# MSP-EXP430FR5994_EagleCAD.net
KiCad netlist of a schematic drawn in EAGLE
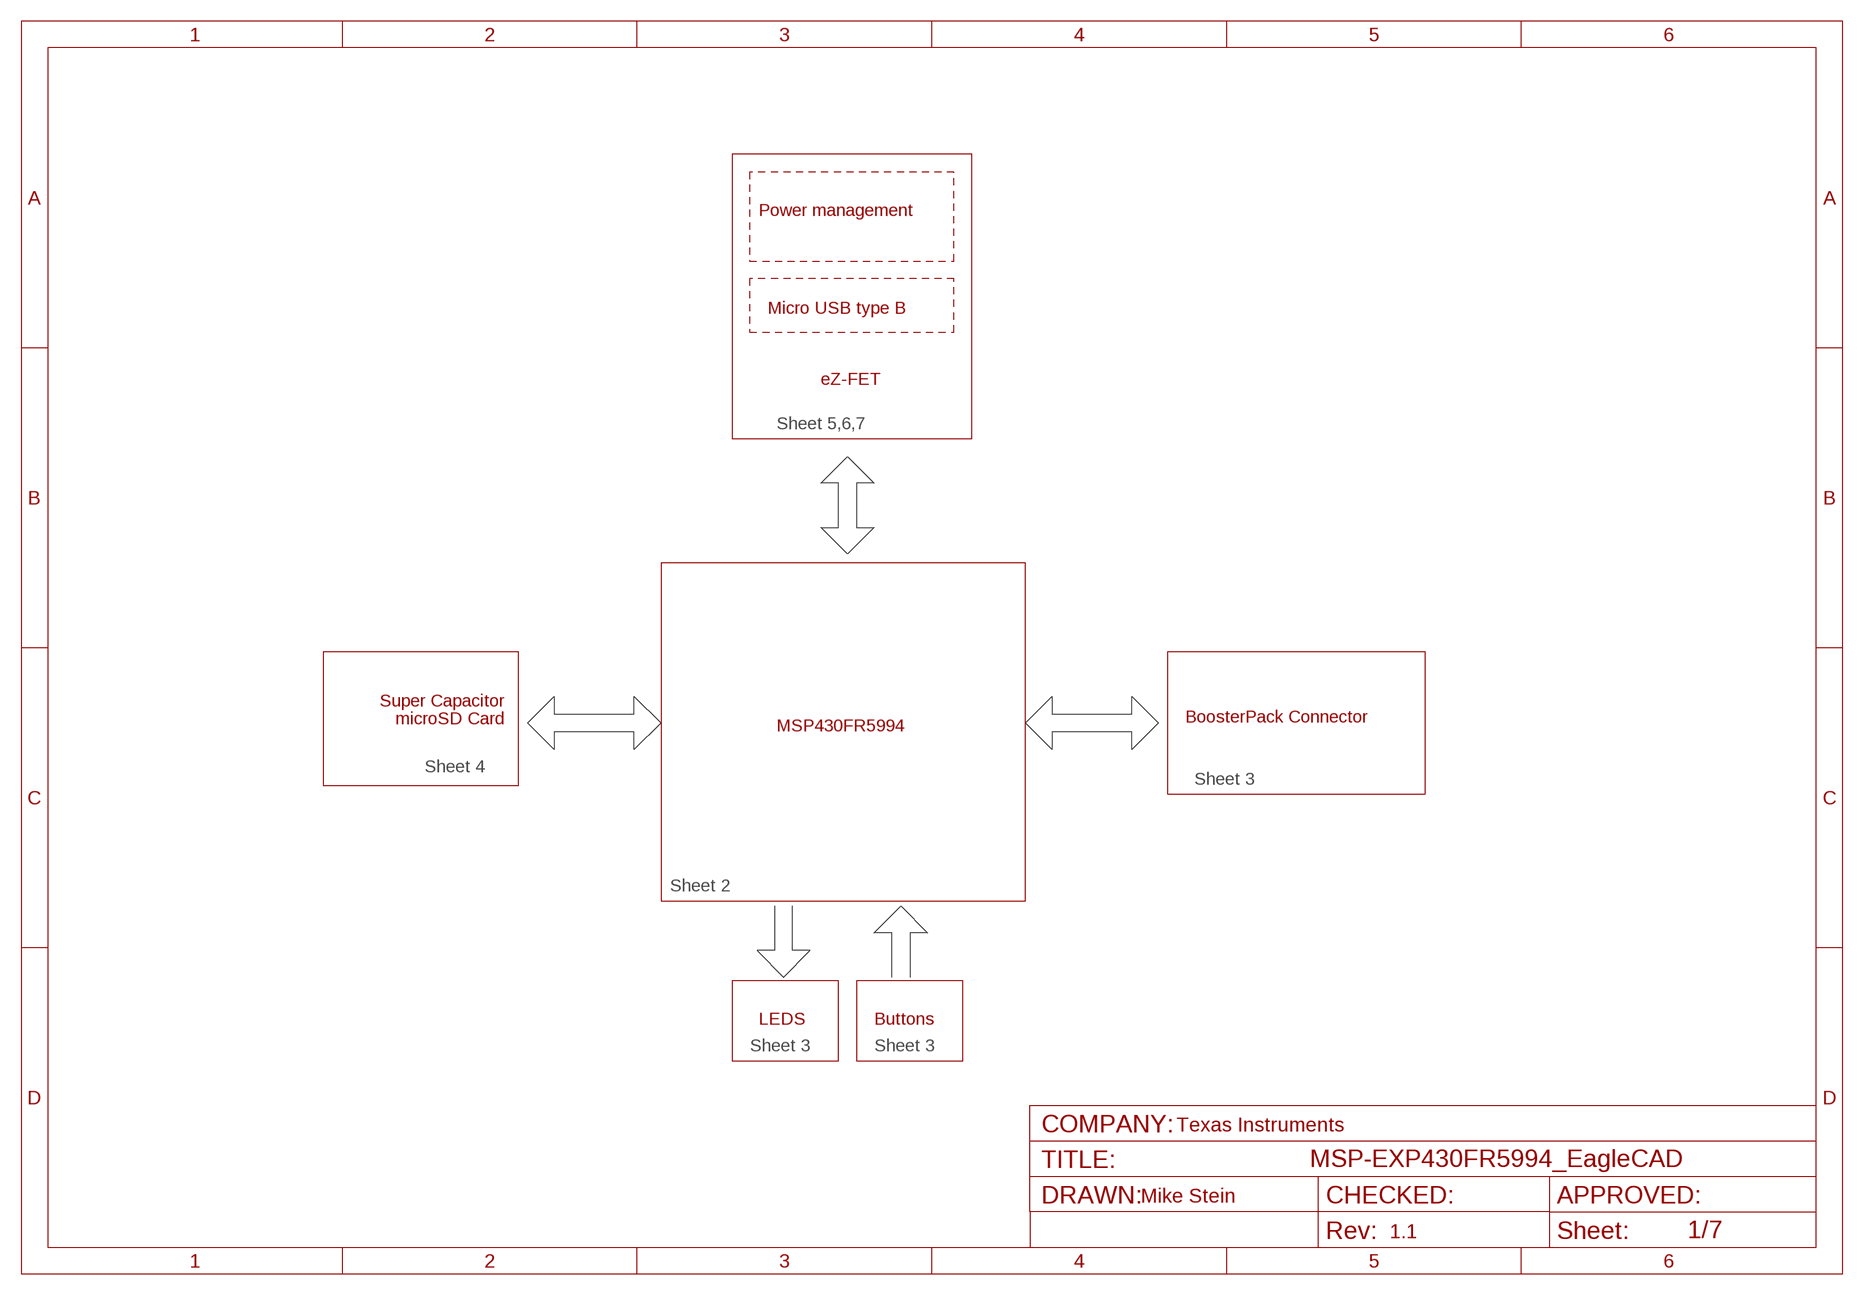
[diagram p0: schematic, sheet 1]
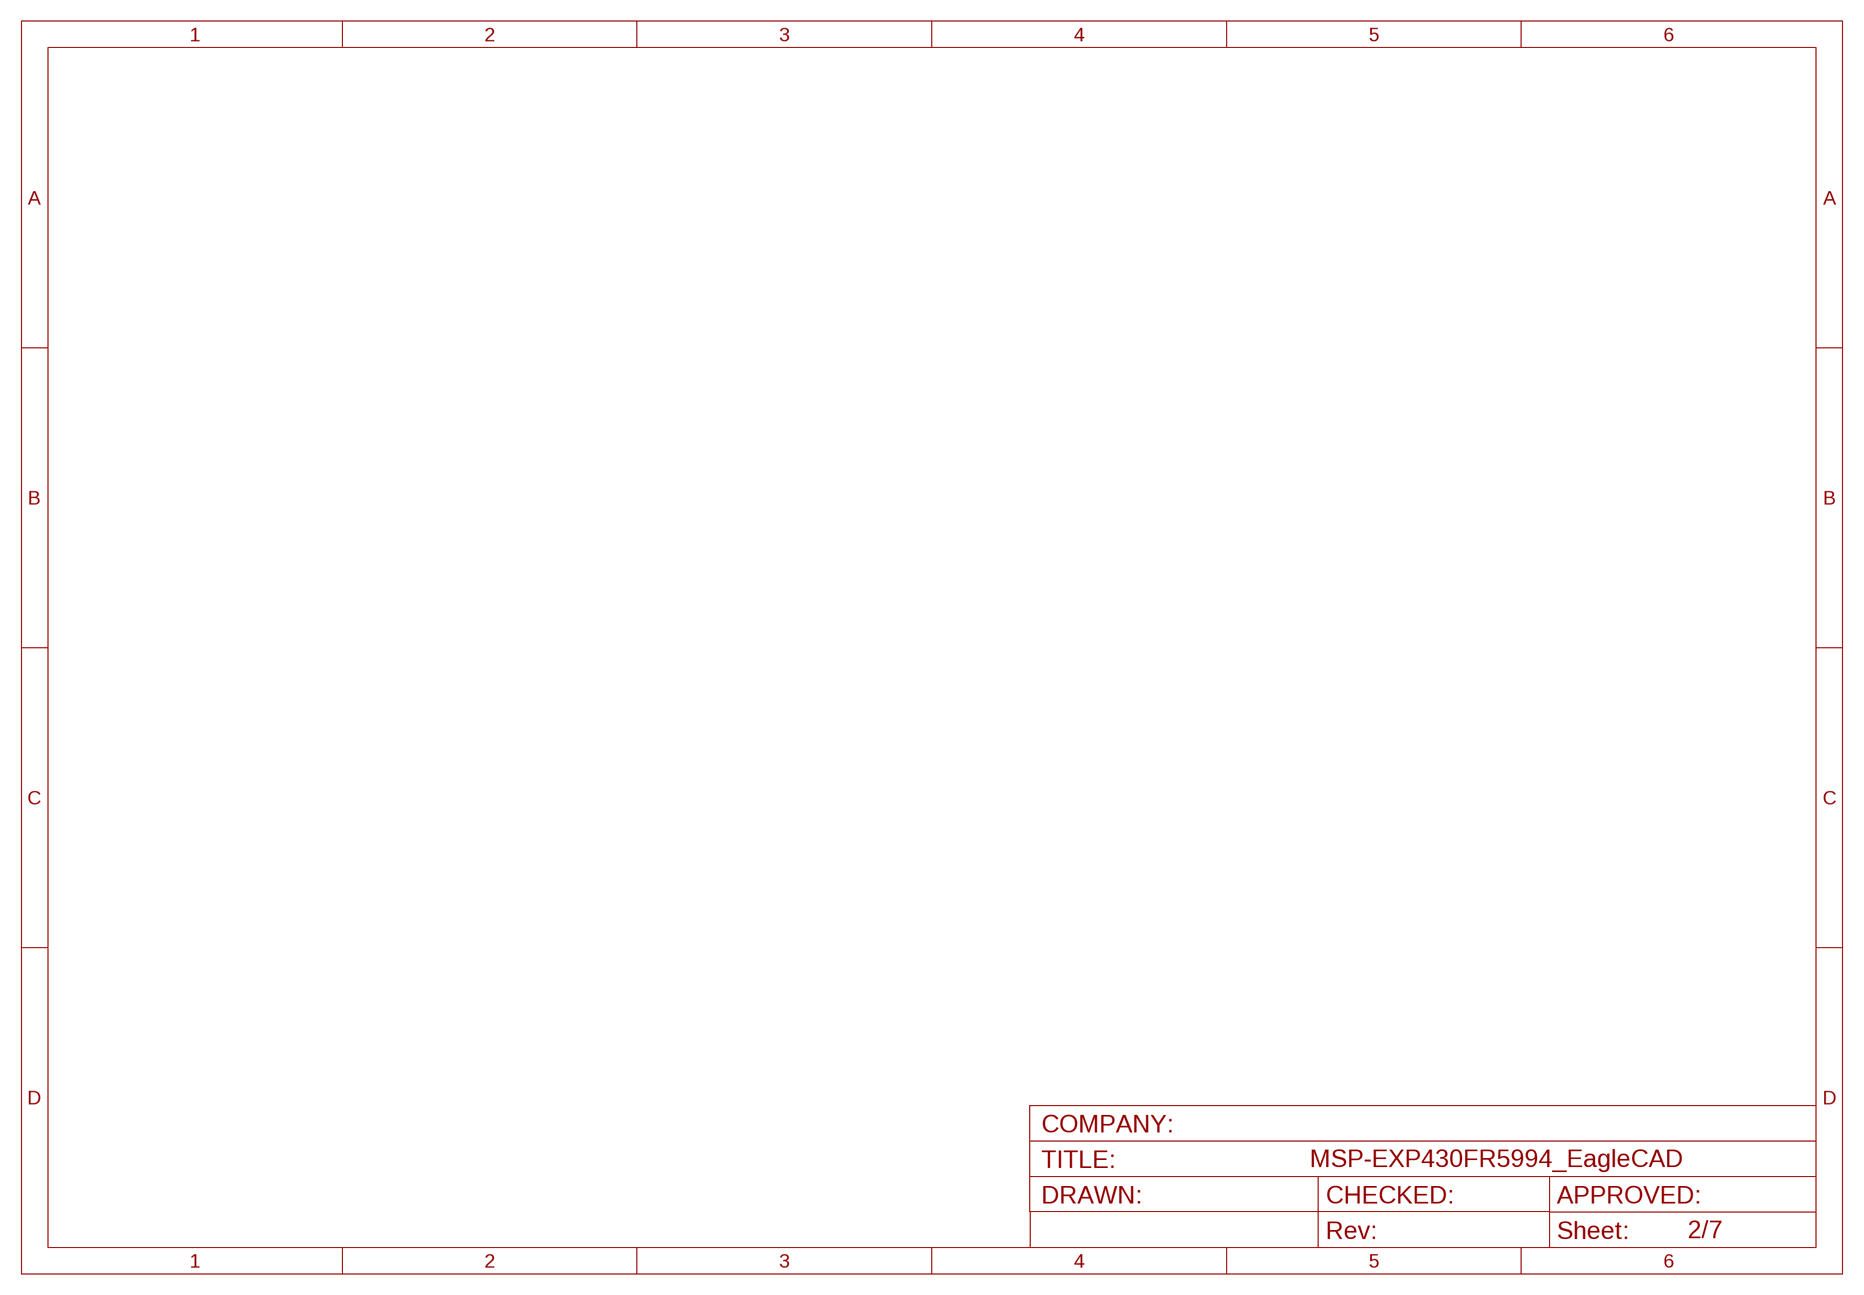
[diagram p1: schematic, sheet 2]
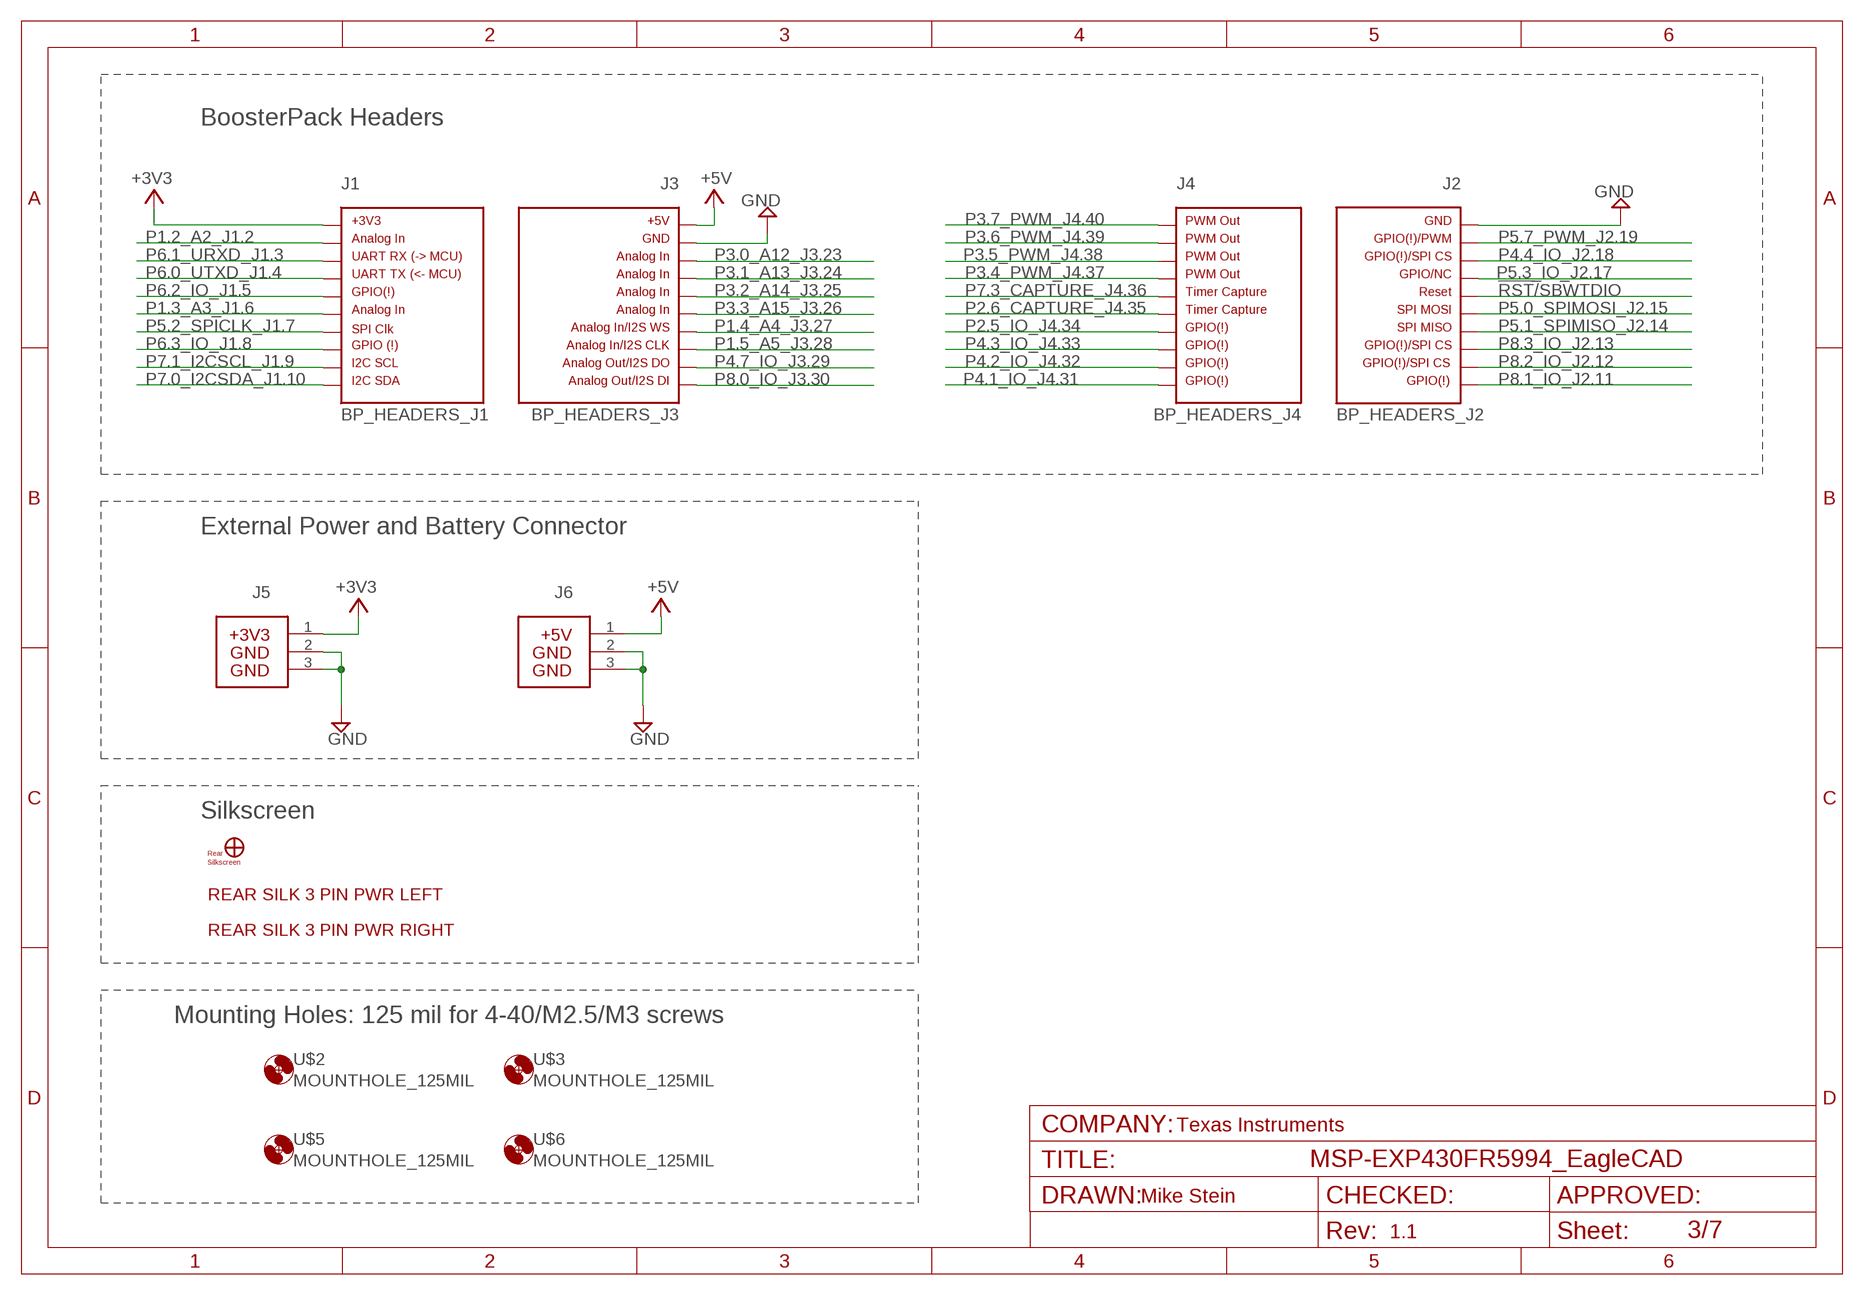
[diagram p2: schematic, sheet 3]
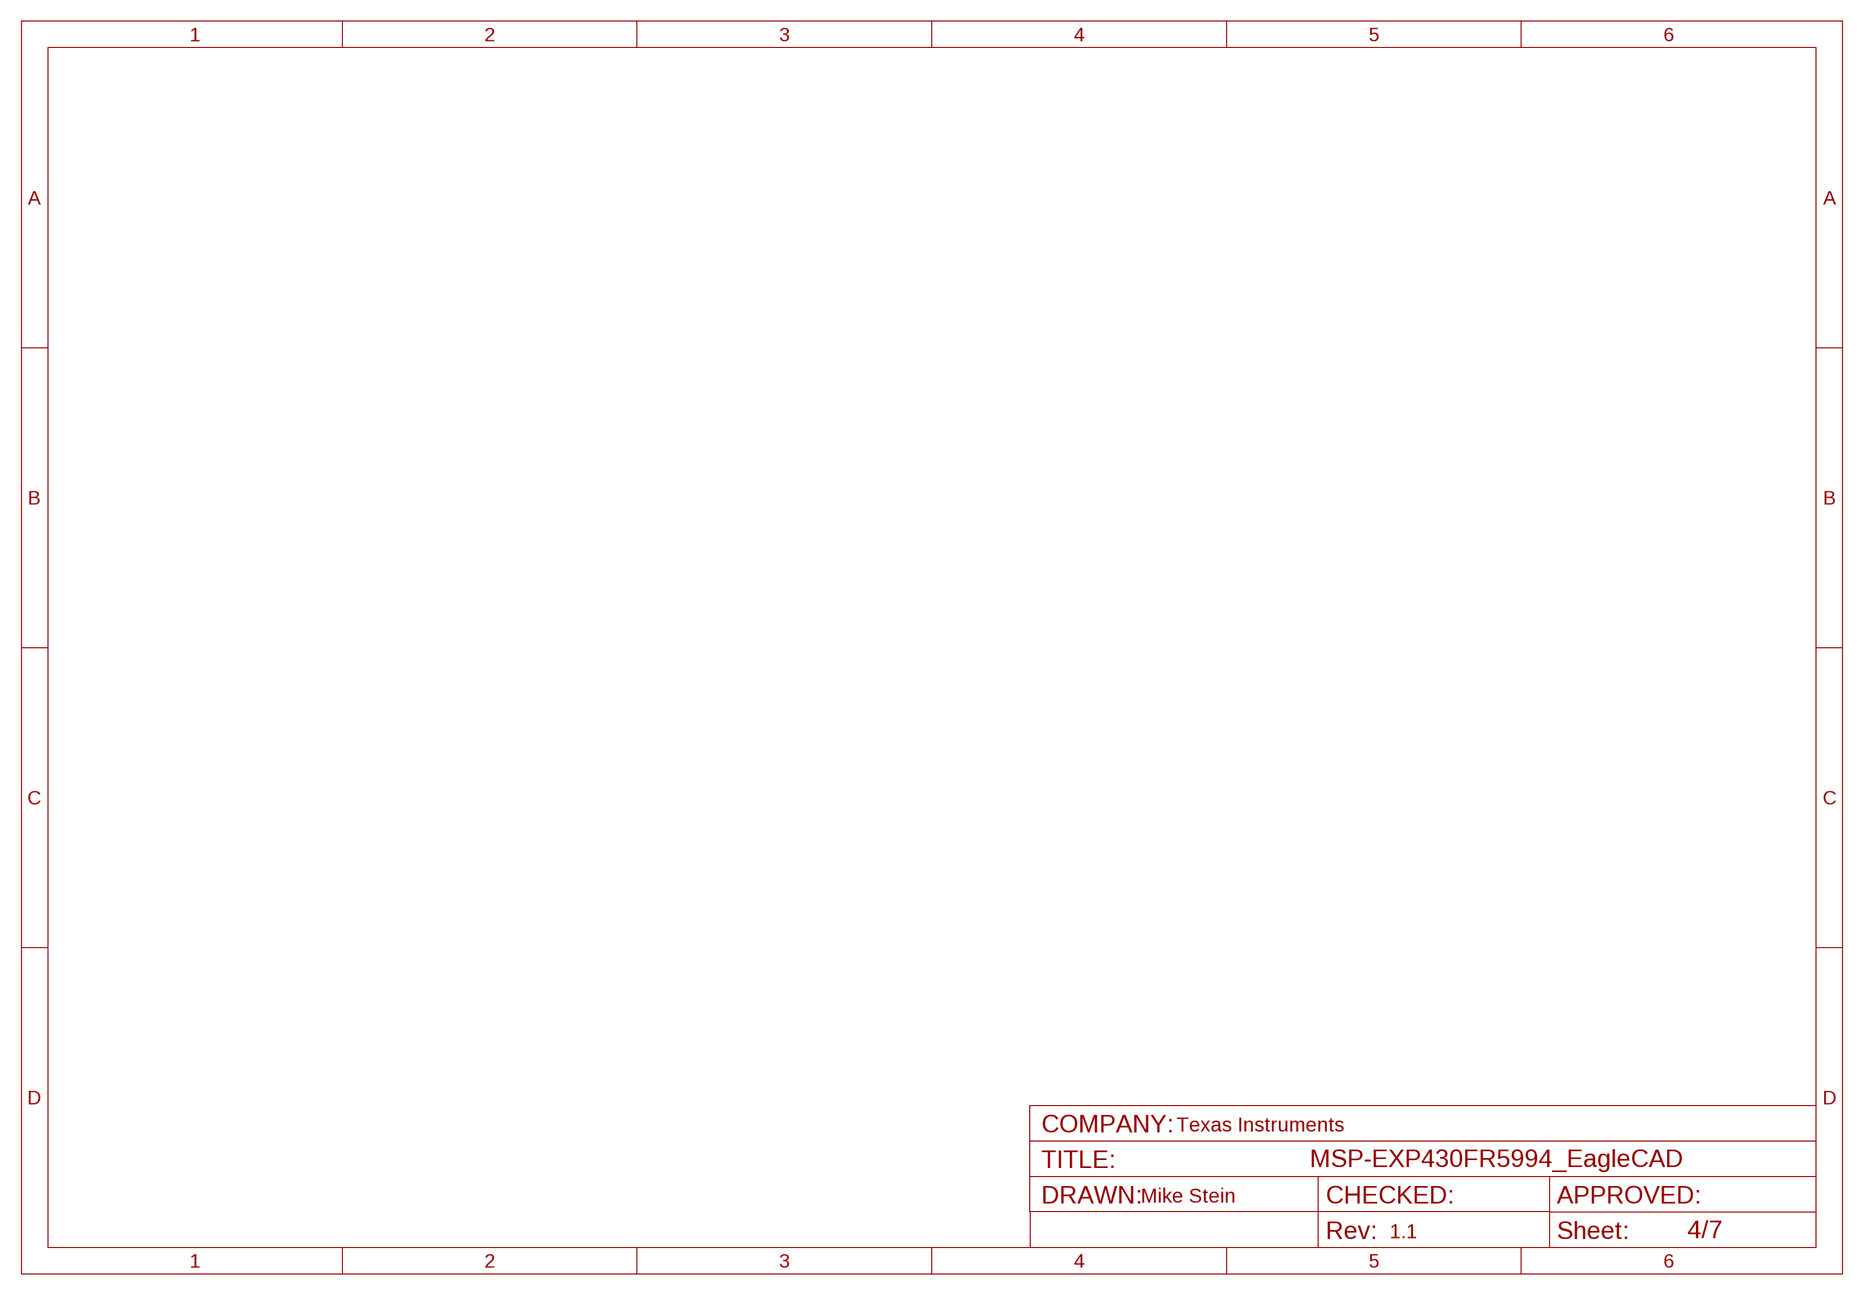
[diagram p3: schematic, sheet 4]
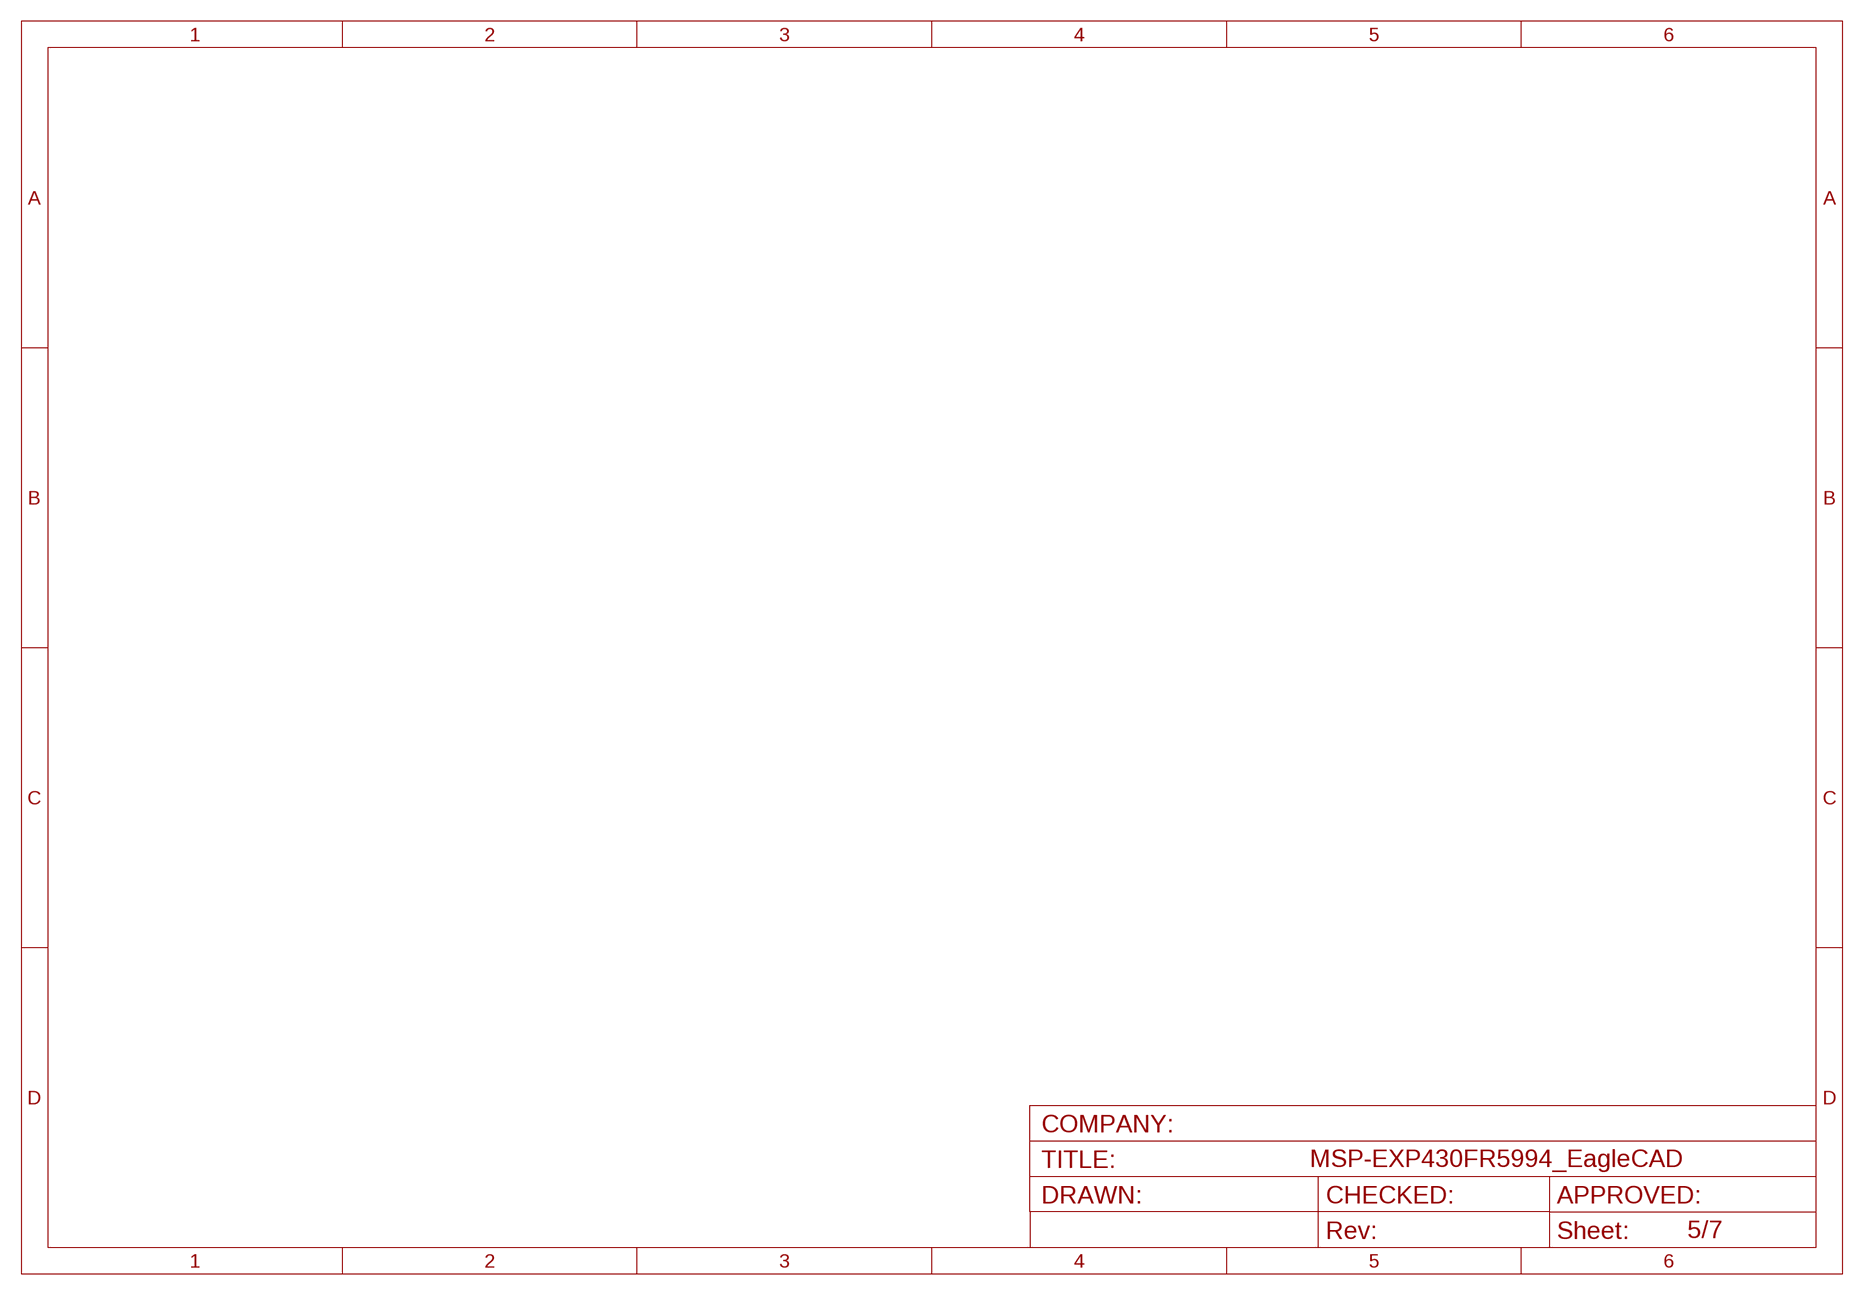
[diagram p4: schematic, sheet 5]
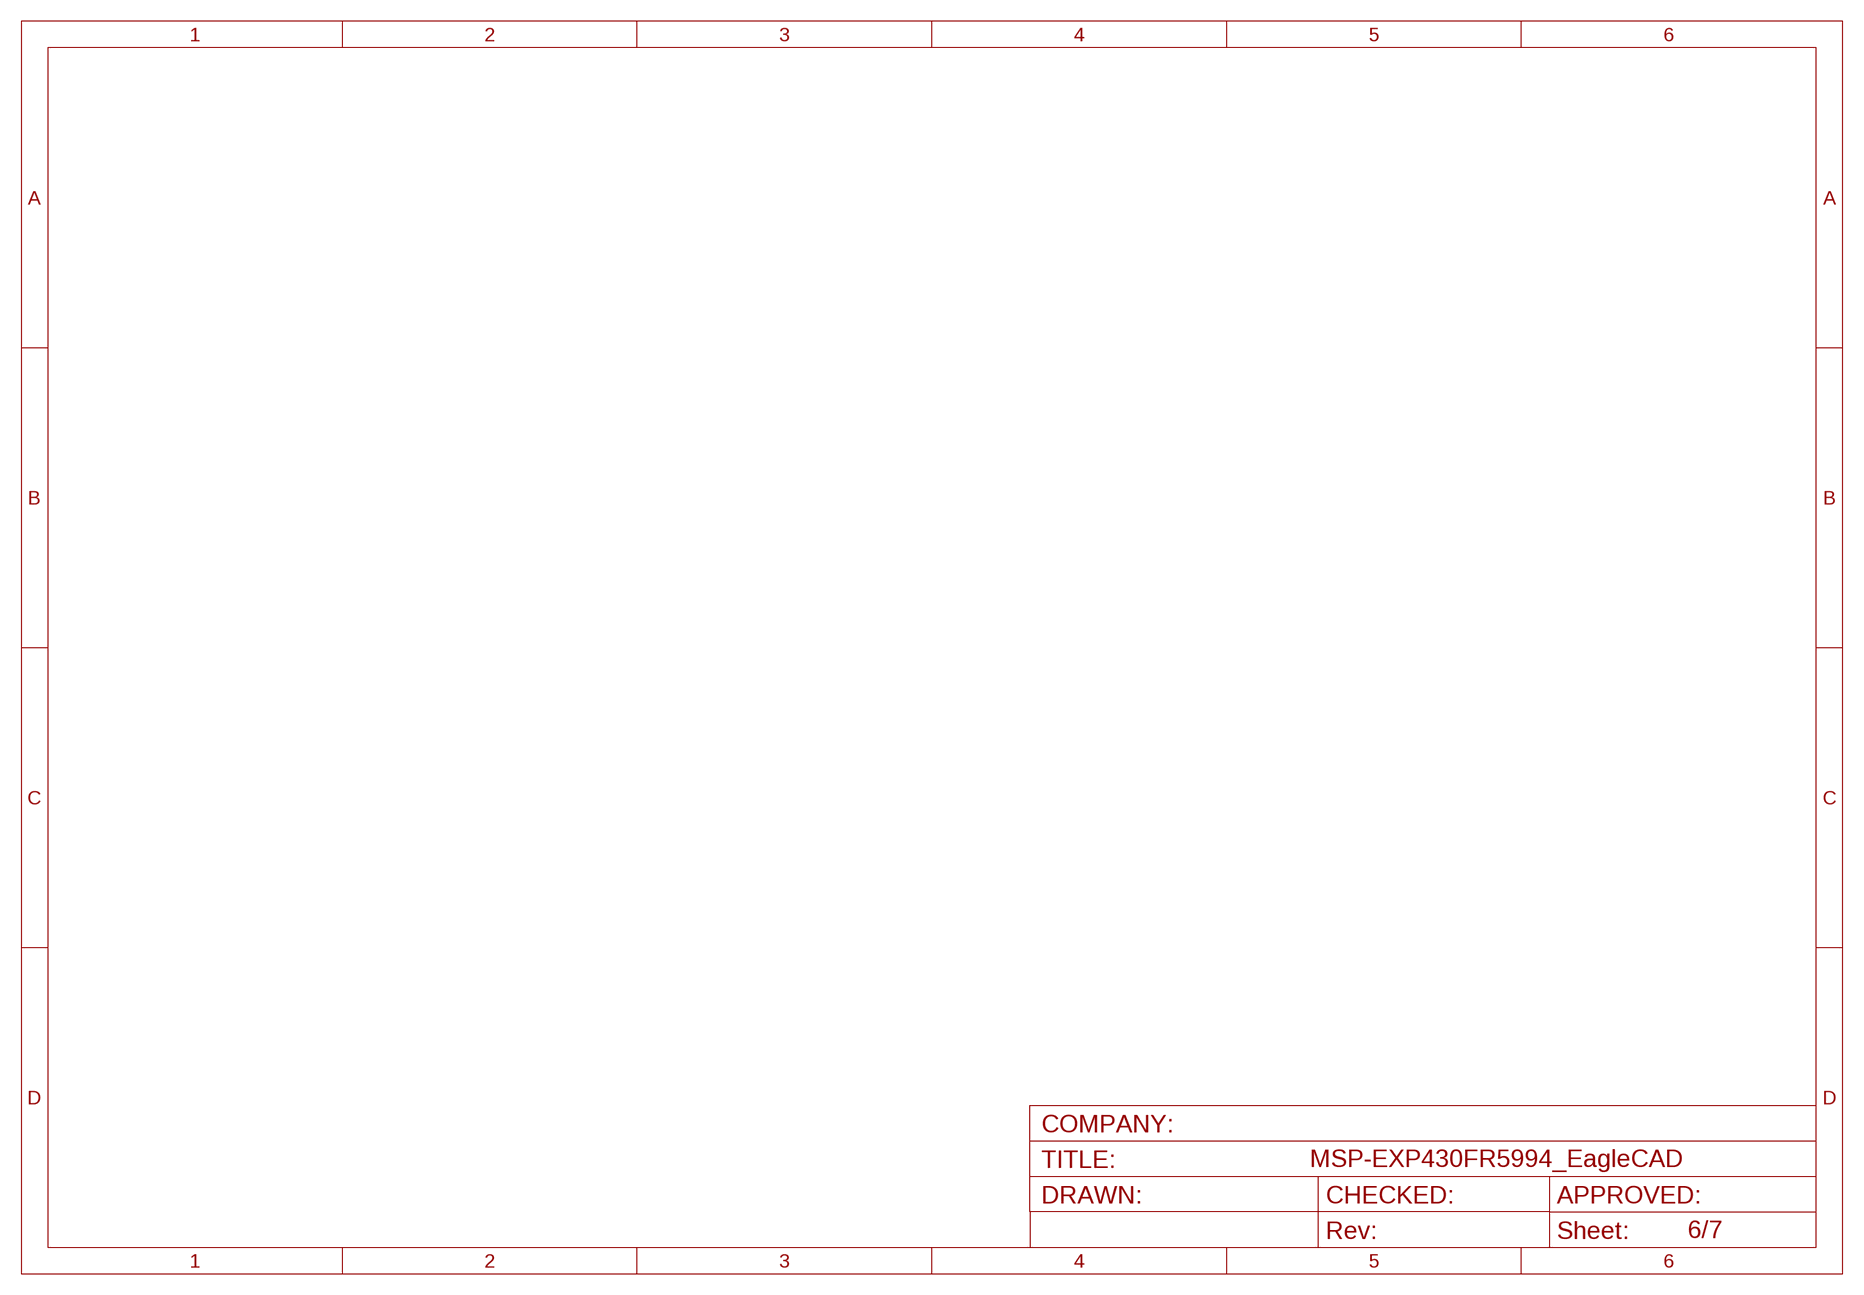
[diagram p5: schematic, sheet 6]
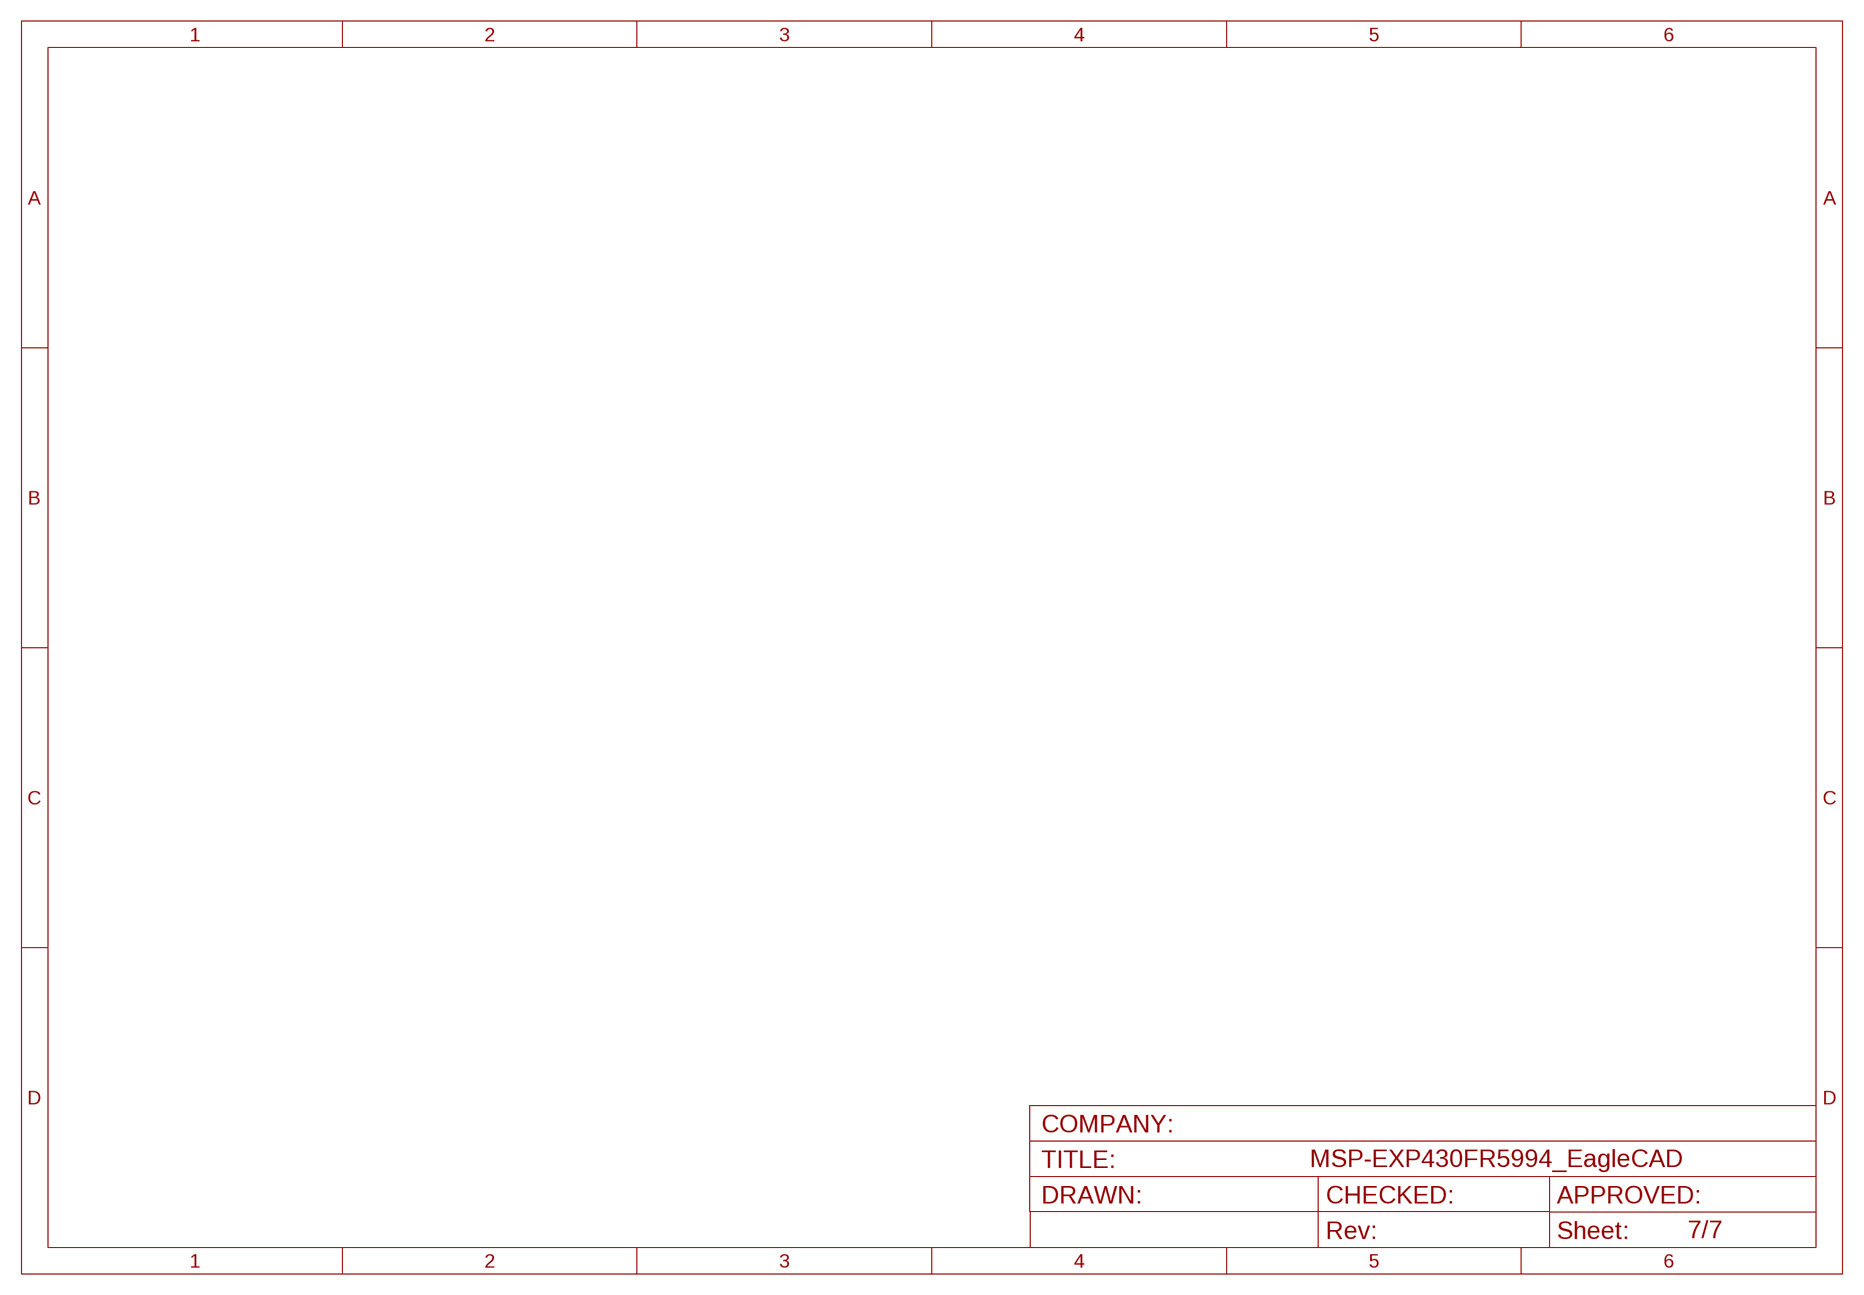
[diagram p6: schematic, sheet 7]

(export (version "E")
  (design (tool "Eeschema 10.0.6"))
  (components
    (comp (ref "J1")
      (value "BP_HEADERS_J1")
      (footprint "eagle-import:J1")
      (libsource (lib "eagle-import") (part "BP_HEADERS_J1"))
    )
    (comp (ref "J2")
      (value "BP_HEADERS_J2")
      (footprint "eagle-import:J2")
      (libsource (lib "eagle-import") (part "BP_HEADERS_J2"))
    )
    (comp (ref "J3")
      (value "BP_HEADERS_J3")
      (footprint "eagle-import:J3")
      (libsource (lib "eagle-import") (part "BP_HEADERS_J3"))
    )
    (comp (ref "J4")
      (value "BP_HEADERS_J4")
      (footprint "eagle-import:J4")
      (libsource (lib "eagle-import") (part "BP_HEADERS_J4"))
    )
    (comp (ref "J5")
      (value "HEADER 1X03")
      (footprint "eagle-import:3PIN_PWR_3V3")
      (libsource (lib "eagle-import") (part "BP_HEADERS_PWR_3V3-TH100"))
    )
    (comp (ref "J6")
      (value "BP_HEADERS_PWR_5V")
      (footprint "eagle-import:3PIN_PWR_5V")
      (libsource (lib "eagle-import") (part "BP_HEADERS_PWR_5V"))
    )
    (comp (ref "U$1")
      (value "FR5994_REARSILK_REV1_0")
      (footprint "eagle-import:FR5994_REARSILK_REV1_0")
      (libsource (lib "eagle-import") (part "FR5994_REARSILK_REV1_0"))
    )
    (comp (ref "U$2")
      (value "MOUNTHOLE_125MIL")
      (footprint "eagle-import:MOUNTHOLE_125MIL")
      (libsource (lib "eagle-import") (part "MOUNTHOLE_125MIL"))
    )
    (comp (ref "U$3")
      (value "MOUNTHOLE_125MIL")
      (footprint "eagle-import:MOUNTHOLE_125MIL")
      (libsource (lib "eagle-import") (part "MOUNTHOLE_125MIL"))
    )
    (comp (ref "U$5")
      (value "MOUNTHOLE_125MIL")
      (footprint "eagle-import:MOUNTHOLE_125MIL")
      (libsource (lib "eagle-import") (part "MOUNTHOLE_125MIL"))
    )
    (comp (ref "U$6")
      (value "MOUNTHOLE_125MIL")
      (footprint "eagle-import:MOUNTHOLE_125MIL")
      (libsource (lib "eagle-import") (part "MOUNTHOLE_125MIL"))
    )
    (comp (ref "U$7")
      (value "MIKE_TM")
      (footprint "eagle-import:MIKE_TM")
      (libsource (lib "eagle-import") (part "MIKE_TM"))
    )
    (comp (ref "U$8")
      (value "BP_3PIN_SILK")
      (footprint "eagle-import:3PIN_PWR_SILK")
      (libsource (lib "eagle-import") (part "BP_3PIN_SILK"))
    )
    (comp (ref "U$10")
      (value "BP_3PIN_SILK_RT")
      (footprint "eagle-import:3PIN_PWR_SILK_RT")
      (libsource (lib "eagle-import") (part "BP_3PIN_SILK_RT"))
    )
  )
  (nets
    (net (code "1") (name "+3V3") (class "Default")
      (node (ref "J1") (pin "1") (pinfunction "1_1") (pintype "bidirectional"))
      (node (ref "J5") (pin "1") (pinfunction "1_1") (pintype "bidirectional"))
    )
    (net (code "2") (name "+5V") (class "Default")
      (node (ref "J3") (pin "21") (pinfunction "21_21") (pintype "bidirectional"))
      (node (ref "J6") (pin "1") (pinfunction "1_1") (pintype "bidirectional"))
    )
    (net (code "3") (name "GND") (class "Default")
      (node (ref "J2") (pin "20") (pinfunction "20_20") (pintype "bidirectional"))
      (node (ref "J3") (pin "22") (pinfunction "22_22") (pintype "bidirectional"))
      (node (ref "J5") (pin "2") (pinfunction "2_2") (pintype "bidirectional"))
      (node (ref "J5") (pin "3") (pinfunction "3_3") (pintype "bidirectional"))
      (node (ref "J6") (pin "2") (pinfunction "2_2") (pintype "bidirectional"))
      (node (ref "J6") (pin "3") (pinfunction "3_3") (pintype "bidirectional"))
    )
    (net (code "4") (name "P1.2_A2_J1.2") (class "Default")
      (node (ref "J1") (pin "2") (pinfunction "2_2") (pintype "bidirectional"))
    )
    (net (code "5") (name "P1.3_A3_J1.6") (class "Default")
      (node (ref "J1") (pin "6") (pinfunction "6_6") (pintype "bidirectional"))
    )
    (net (code "6") (name "P1.4_A4_J3.27") (class "Default")
      (node (ref "J3") (pin "27") (pinfunction "27_27") (pintype "bidirectional"))
    )
    (net (code "7") (name "P1.5_A5_J3.28") (class "Default")
      (node (ref "J3") (pin "28") (pinfunction "28_28") (pintype "bidirectional"))
    )
    (net (code "8") (name "P2.5_IO_J4.34") (class "Default")
      (node (ref "J4") (pin "34") (pinfunction "34_34") (pintype "bidirectional"))
    )
    (net (code "9") (name "P2.6_CAPTURE_J4.35") (class "Default")
      (node (ref "J4") (pin "35") (pinfunction "35_35") (pintype "bidirectional"))
    )
    (net (code "10") (name "P3.0_A12_J3.23") (class "Default")
      (node (ref "J3") (pin "23") (pinfunction "23_23") (pintype "bidirectional"))
    )
    (net (code "11") (name "P3.1_A13_J3.24") (class "Default")
      (node (ref "J3") (pin "24") (pinfunction "24_24") (pintype "bidirectional"))
    )
    (net (code "12") (name "P3.2_A14_J3.25") (class "Default")
      (node (ref "J3") (pin "25") (pinfunction "25_25") (pintype "bidirectional"))
    )
    (net (code "13") (name "P3.3_A15_J3.26") (class "Default")
      (node (ref "J3") (pin "26") (pinfunction "26_26") (pintype "bidirectional"))
    )
    (net (code "14") (name "P3.4_PWM_J4.37") (class "Default")
      (node (ref "J4") (pin "37") (pinfunction "37_37") (pintype "bidirectional"))
    )
    (net (code "15") (name "P3.5_PWM_J4.38") (class "Default")
      (node (ref "J4") (pin "38") (pinfunction "38_38") (pintype "bidirectional"))
    )
    (net (code "16") (name "P3.6_PWM_J4.39") (class "Default")
      (node (ref "J4") (pin "39") (pinfunction "39_39") (pintype "bidirectional"))
    )
    (net (code "17") (name "P3.7_PWM_J4.40") (class "Default")
      (node (ref "J4") (pin "40") (pinfunction "40_40") (pintype "bidirectional"))
    )
    (net (code "18") (name "P4.1_IO_J4.31") (class "Default")
      (node (ref "J4") (pin "31") (pinfunction "31_31") (pintype "bidirectional"))
    )
    (net (code "19") (name "P4.2_IO_J4.32") (class "Default")
      (node (ref "J4") (pin "32") (pinfunction "32_32") (pintype "bidirectional"))
    )
    (net (code "20") (name "P4.3_IO_J4.33") (class "Default")
      (node (ref "J4") (pin "33") (pinfunction "33_33") (pintype "bidirectional"))
    )
    (net (code "21") (name "P4.4_IO_J2.18") (class "Default")
      (node (ref "J2") (pin "18") (pinfunction "18_18") (pintype "bidirectional"))
    )
    (net (code "22") (name "P4.7_IO_J3.29") (class "Default")
      (node (ref "J3") (pin "29") (pinfunction "29_29") (pintype "bidirectional"))
    )
    (net (code "23") (name "P5.0_SPIMOSI_J2.15") (class "Default")
      (node (ref "J2") (pin "15") (pinfunction "15_15") (pintype "bidirectional"))
    )
    (net (code "24") (name "P5.1_SPIMISO_J2.14") (class "Default")
      (node (ref "J2") (pin "14") (pinfunction "14_14") (pintype "bidirectional"))
    )
    (net (code "25") (name "P5.2_SPICLK_J1.7") (class "Default")
      (node (ref "J1") (pin "7") (pinfunction "7_7") (pintype "bidirectional"))
    )
    (net (code "26") (name "P5.3_IO_J2.17") (class "Default")
      (node (ref "J2") (pin "17") (pinfunction "17_17") (pintype "bidirectional"))
    )
    (net (code "27") (name "P5.7_PWM_J2.19") (class "Default")
      (node (ref "J2") (pin "19") (pinfunction "19_19") (pintype "bidirectional"))
    )
    (net (code "28") (name "P6.0_UTXD_J1.4") (class "Default")
      (node (ref "J1") (pin "4") (pinfunction "4_4") (pintype "bidirectional"))
    )
    (net (code "29") (name "P6.1_URXD_J1.3") (class "Default")
      (node (ref "J1") (pin "3") (pinfunction "3_3") (pintype "bidirectional"))
    )
    (net (code "30") (name "P6.2_IO_J1.5") (class "Default")
      (node (ref "J1") (pin "5") (pinfunction "5_5") (pintype "bidirectional"))
    )
    (net (code "31") (name "P6.3_IO_J1.8") (class "Default")
      (node (ref "J1") (pin "8") (pinfunction "8_8") (pintype "bidirectional"))
    )
    (net (code "32") (name "P7.0_I2CSDA_J1.10") (class "Default")
      (node (ref "J1") (pin "10") (pinfunction "10_10") (pintype "bidirectional"))
    )
    (net (code "33") (name "P7.1_I2CSCL_J1.9") (class "Default")
      (node (ref "J1") (pin "9") (pinfunction "9_9") (pintype "bidirectional"))
    )
    (net (code "34") (name "P7.3_CAPTURE_J4.36") (class "Default")
      (node (ref "J4") (pin "36") (pinfunction "36_36") (pintype "bidirectional"))
    )
    (net (code "35") (name "P8.0_IO_J3.30") (class "Default")
      (node (ref "J3") (pin "30") (pinfunction "30_30") (pintype "bidirectional"))
    )
    (net (code "36") (name "P8.1_IO_J2.11") (class "Default")
      (node (ref "J2") (pin "11") (pinfunction "11_11") (pintype "bidirectional"))
    )
    (net (code "37") (name "P8.2_IO_J2.12") (class "Default")
      (node (ref "J2") (pin "12") (pinfunction "12_12") (pintype "bidirectional"))
    )
    (net (code "38") (name "P8.3_IO_J2.13") (class "Default")
      (node (ref "J2") (pin "13") (pinfunction "13_13") (pintype "bidirectional"))
    )
    (net (code "39") (name "~{RST}{slash}SBWTDIO") (class "Default")
      (node (ref "J2") (pin "16") (pinfunction "16_16") (pintype "bidirectional"))
    )
  )
)
